# esquema_synesthesia.net
KiCad netlist of a schematic drawn in EAGLE
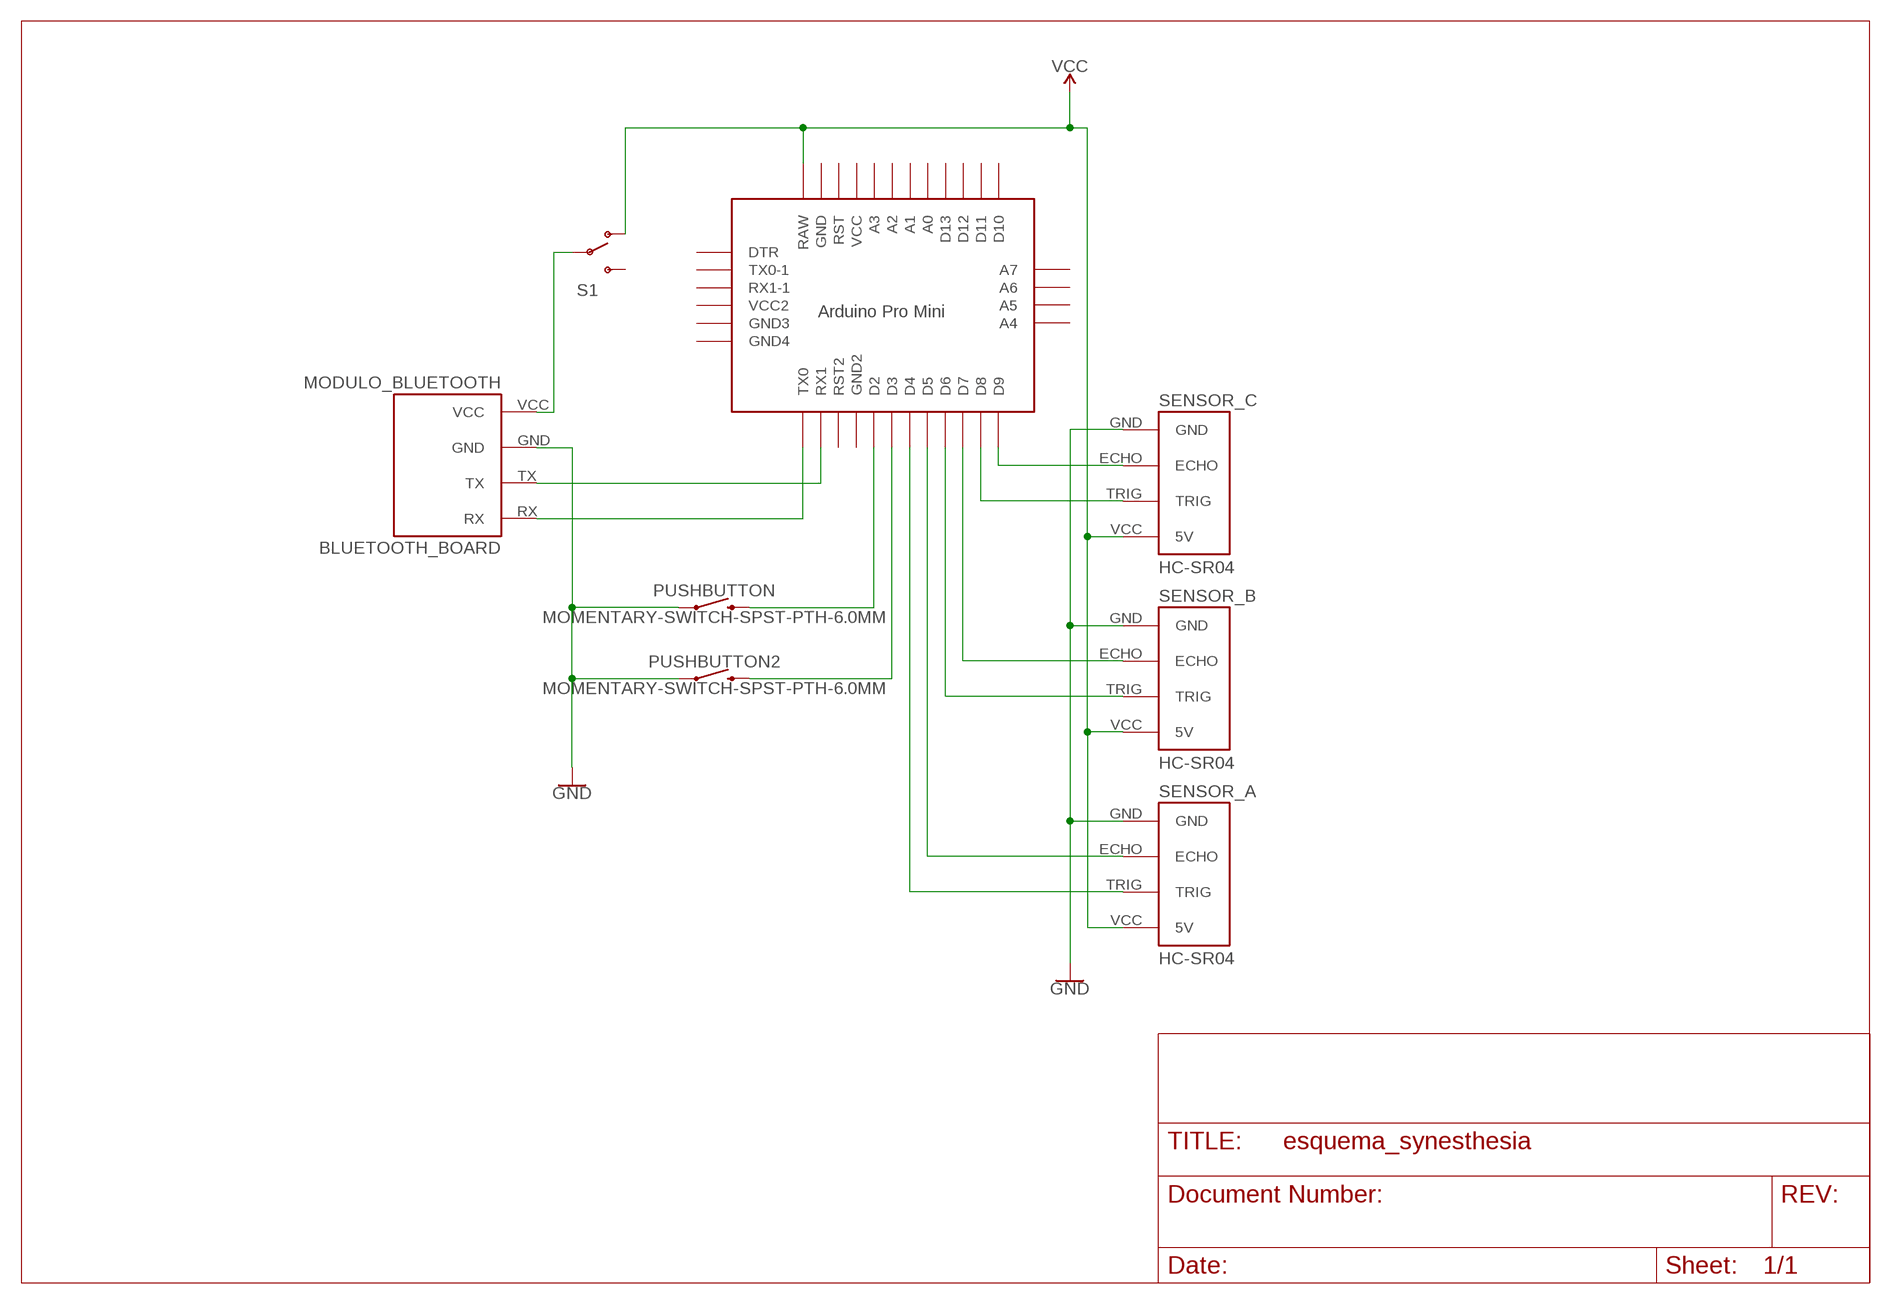
[diagram p0: schematic, sheet 1]

(export (version "E")
  (design (tool "Eeschema 10.0.6"))
  (components
    (comp (ref "MODULO_BLUETOOTH")
      (value "BLUETOOTH_BOARD")
      (footprint "eagle-import:BT_BOARD_FOOTPRINT")
      (libsource (lib "eagle-import") (part "BLUETOOTH_BOARD"))
    )
    (comp (ref "PUSHBUTTON")
      (value "MOMENTARY-SWITCH-SPST-PTH-6.0MM")
      (footprint "eagle-import:TACTILE_SWITCH_PTH_6.0MM")
      (libsource (lib "eagle-import") (part "MOMENTARY-SWITCH-SPST-PTH-6.0MM"))
    )
    (comp (ref "PUSHBUTTON2")
      (value "MOMENTARY-SWITCH-SPST-PTH-6.0MM")
      (footprint "eagle-import:TACTILE_SWITCH_PTH_6.0MM")
      (libsource (lib "eagle-import") (part "MOMENTARY-SWITCH-SPST-PTH-6.0MM"))
    )
    (comp (ref "S1")
      (value "SWITCH-SPDTPTH2")
      (footprint "eagle-import:SWITCH-DPDT")
      (libsource (lib "eagle-import") (part "SWITCH-SPDTPTH2"))
    )
    (comp (ref "SENSOR_A")
      (value "HC-SR04")
      (footprint "eagle-import:HC-SR04_FOOTPRINT")
      (libsource (lib "eagle-import") (part "HC-SR04"))
    )
    (comp (ref "SENSOR_B")
      (value "HC-SR04")
      (footprint "eagle-import:HC-SR04_FOOTPRINT")
      (libsource (lib "eagle-import") (part "HC-SR04"))
    )
    (comp (ref "SENSOR_C")
      (value "HC-SR04")
      (footprint "eagle-import:HC-SR04_FOOTPRINT")
      (libsource (lib "eagle-import") (part "HC-SR04"))
    )
    (comp (ref "U$1")
      (value "PRO-MINI")
      (footprint "eagle-import:PRO-MINI")
      (libsource (lib "eagle-import") (part "PRO-MINI"))
    )
  )
  (nets
    (net (code "1") (name "GND") (class "Default")
      (node (ref "MODULO_BLUETOOTH") (pin "GND") (pinfunction "GND_GND") (pintype "bidirectional"))
      (node (ref "PUSHBUTTON") (pin "1") (pinfunction "1_1") (pintype "passive"))
      (node (ref "PUSHBUTTON2") (pin "1") (pinfunction "1_1") (pintype "passive"))
      (node (ref "SENSOR_A") (pin "GND") (pinfunction "GND_GND") (pintype "bidirectional"))
      (node (ref "SENSOR_B") (pin "GND") (pinfunction "GND_GND") (pintype "bidirectional"))
      (node (ref "SENSOR_C") (pin "GND") (pinfunction "GND_GND") (pintype "bidirectional"))
    )
    (net (code "2") (name "Net-(MODULO_BLUETOOTH-PadRX)") (class "Default")
      (node (ref "MODULO_BLUETOOTH") (pin "RX") (pinfunction "RX_RX") (pintype "bidirectional"))
      (node (ref "U$1") (pin "TX0") (pinfunction "TX0_TX0") (pintype "bidirectional"))
    )
    (net (code "3") (name "Net-(MODULO_BLUETOOTH-PadTX)") (class "Default")
      (node (ref "MODULO_BLUETOOTH") (pin "TX") (pinfunction "TX_TX") (pintype "bidirectional"))
      (node (ref "U$1") (pin "RX1") (pinfunction "RX1_RX1") (pintype "bidirectional"))
    )
    (net (code "4") (name "Net-(PUSHBUTTON-2)") (class "Default")
      (node (ref "PUSHBUTTON") (pin "3") (pinfunction "2_3") (pintype "passive"))
      (node (ref "U$1") (pin "D2") (pinfunction "D2_D2") (pintype "bidirectional"))
    )
    (net (code "5") (name "Net-(PUSHBUTTON2-2)") (class "Default")
      (node (ref "PUSHBUTTON2") (pin "3") (pinfunction "2_3") (pintype "passive"))
      (node (ref "U$1") (pin "D3") (pinfunction "D3_D3") (pintype "bidirectional"))
    )
    (net (code "6") (name "Net-(S1-P)") (class "Default")
      (node (ref "MODULO_BLUETOOTH") (pin "VCC") (pinfunction "VCC_VCC") (pintype "bidirectional"))
      (node (ref "S1") (pin "2") (pinfunction "P_2") (pintype "passive"))
    )
    (net (code "7") (name "Net-(SENSOR_A-PadECHO)") (class "Default")
      (node (ref "SENSOR_A") (pin "ECHO") (pinfunction "ECHO_ECHO") (pintype "bidirectional"))
      (node (ref "U$1") (pin "D5") (pinfunction "D5_D5") (pintype "bidirectional"))
    )
    (net (code "8") (name "Net-(SENSOR_A-PadTRIG)") (class "Default")
      (node (ref "SENSOR_A") (pin "TRIG") (pinfunction "TRIG_TRIG") (pintype "bidirectional"))
      (node (ref "U$1") (pin "D4") (pinfunction "D4_D4") (pintype "bidirectional"))
    )
    (net (code "9") (name "Net-(SENSOR_B-PadECHO)") (class "Default")
      (node (ref "SENSOR_B") (pin "ECHO") (pinfunction "ECHO_ECHO") (pintype "bidirectional"))
      (node (ref "U$1") (pin "D7") (pinfunction "D7_D7") (pintype "bidirectional"))
    )
    (net (code "10") (name "Net-(SENSOR_B-PadTRIG)") (class "Default")
      (node (ref "SENSOR_B") (pin "TRIG") (pinfunction "TRIG_TRIG") (pintype "bidirectional"))
      (node (ref "U$1") (pin "D6") (pinfunction "D6_D6") (pintype "bidirectional"))
    )
    (net (code "11") (name "Net-(SENSOR_C-PadECHO)") (class "Default")
      (node (ref "SENSOR_C") (pin "ECHO") (pinfunction "ECHO_ECHO") (pintype "bidirectional"))
      (node (ref "U$1") (pin "D9") (pinfunction "D9_D9") (pintype "bidirectional"))
    )
    (net (code "12") (name "Net-(SENSOR_C-PadTRIG)") (class "Default")
      (node (ref "SENSOR_C") (pin "TRIG") (pinfunction "TRIG_TRIG") (pintype "bidirectional"))
      (node (ref "U$1") (pin "D8") (pinfunction "D8_D8") (pintype "bidirectional"))
    )
    (net (code "13") (name "VCC") (class "Default")
      (node (ref "S1") (pin "1") (pinfunction "O_1") (pintype "passive"))
      (node (ref "SENSOR_A") (pin "VCC") (pinfunction "5V_VCC") (pintype "bidirectional"))
      (node (ref "SENSOR_B") (pin "VCC") (pinfunction "5V_VCC") (pintype "bidirectional"))
      (node (ref "SENSOR_C") (pin "VCC") (pinfunction "5V_VCC") (pintype "bidirectional"))
      (node (ref "U$1") (pin "RAW") (pinfunction "RAW_RAW") (pintype "power_in"))
    )
    (net (code "14") (name "unconnected-(S1-S-Pad3)") (class "Default")
      (node (ref "S1") (pin "3") (pinfunction "S_3") (pintype "passive"))
    )
    (net (code "15") (name "unconnected-(U$1-GND2-PadGND1)") (class "Default")
      (node (ref "U$1") (pin "GND1") (pinfunction "GND2_GND1") (pintype "bidirectional"))
    )
    (net (code "16") (name "unconnected-(U$1-GND4-PadGND2)") (class "Default")
      (node (ref "U$1") (pin "GND2") (pinfunction "GND4_GND2") (pintype "bidirectional"))
    )
    (net (code "17") (name "unconnected-(U$1-PadA0)") (class "Default")
      (node (ref "U$1") (pin "A0") (pinfunction "A0_A0") (pintype "bidirectional"))
    )
    (net (code "18") (name "unconnected-(U$1-PadA1)") (class "Default")
      (node (ref "U$1") (pin "A1") (pinfunction "A1_A1") (pintype "bidirectional"))
    )
    (net (code "19") (name "unconnected-(U$1-PadA2)") (class "Default")
      (node (ref "U$1") (pin "A2") (pinfunction "A2_A2") (pintype "bidirectional"))
    )
    (net (code "20") (name "unconnected-(U$1-PadA3)") (class "Default")
      (node (ref "U$1") (pin "A3") (pinfunction "A3_A3") (pintype "bidirectional"))
    )
    (net (code "21") (name "unconnected-(U$1-PadA4)") (class "Default")
      (node (ref "U$1") (pin "A4") (pinfunction "A4_A4") (pintype "bidirectional"))
    )
    (net (code "22") (name "unconnected-(U$1-PadA5)") (class "Default")
      (node (ref "U$1") (pin "A5") (pinfunction "A5_A5") (pintype "bidirectional"))
    )
    (net (code "23") (name "unconnected-(U$1-PadA6)") (class "Default")
      (node (ref "U$1") (pin "A6") (pinfunction "A6_A6") (pintype "bidirectional"))
    )
    (net (code "24") (name "unconnected-(U$1-PadA7)") (class "Default")
      (node (ref "U$1") (pin "A7") (pinfunction "A7_A7") (pintype "bidirectional"))
    )
    (net (code "25") (name "unconnected-(U$1-PadD10)") (class "Default")
      (node (ref "U$1") (pin "D10") (pinfunction "D10_D10") (pintype "bidirectional"))
    )
    (net (code "26") (name "unconnected-(U$1-PadD11)") (class "Default")
      (node (ref "U$1") (pin "D11") (pinfunction "D11_D11") (pintype "bidirectional"))
    )
    (net (code "27") (name "unconnected-(U$1-PadD12)") (class "Default")
      (node (ref "U$1") (pin "D12") (pinfunction "D12_D12") (pintype "bidirectional"))
    )
    (net (code "28") (name "unconnected-(U$1-PadD13)") (class "Default")
      (node (ref "U$1") (pin "D13") (pinfunction "D13_D13") (pintype "bidirectional"))
    )
    (net (code "29") (name "unconnected-(U$1-PadDTR)") (class "Default")
      (node (ref "U$1") (pin "DTR") (pinfunction "DTR_DTR") (pintype "bidirectional"))
    )
    (net (code "30") (name "unconnected-(U$1-PadGND)") (class "Default")
      (node (ref "U$1") (pin "GND") (pinfunction "GND_GND") (pintype "input"))
    )
    (net (code "31") (name "unconnected-(U$1-PadGND3)") (class "Default")
      (node (ref "U$1") (pin "GND3") (pinfunction "GND3_GND3") (pintype "bidirectional"))
    )
    (net (code "32") (name "unconnected-(U$1-PadRST)") (class "Default")
      (node (ref "U$1") (pin "RST") (pinfunction "RST_RST") (pintype "bidirectional"))
    )
    (net (code "33") (name "unconnected-(U$1-PadRX1-1)") (class "Default")
      (node (ref "U$1") (pin "RX1-1") (pinfunction "RX1-1_RX1-1") (pintype "bidirectional"))
    )
    (net (code "34") (name "unconnected-(U$1-PadTX0-1)") (class "Default")
      (node (ref "U$1") (pin "TX0-1") (pinfunction "TX0-1_TX0-1") (pintype "bidirectional"))
    )
    (net (code "35") (name "unconnected-(U$1-PadVCC)") (class "Default")
      (node (ref "U$1") (pin "VCC") (pinfunction "VCC_VCC") (pintype "bidirectional"))
    )
    (net (code "36") (name "unconnected-(U$1-RST2-PadRST1)") (class "Default")
      (node (ref "U$1") (pin "RST1") (pinfunction "RST2_RST1") (pintype "bidirectional"))
    )
    (net (code "37") (name "unconnected-(U$1-VCC2-PadVCC1)") (class "Default")
      (node (ref "U$1") (pin "VCC1") (pinfunction "VCC2_VCC1") (pintype "bidirectional"))
    )
  )
)
